# 5_Current_Voltage_Sensor.net
KiCad netlist of a schematic drawn in Altium Designer
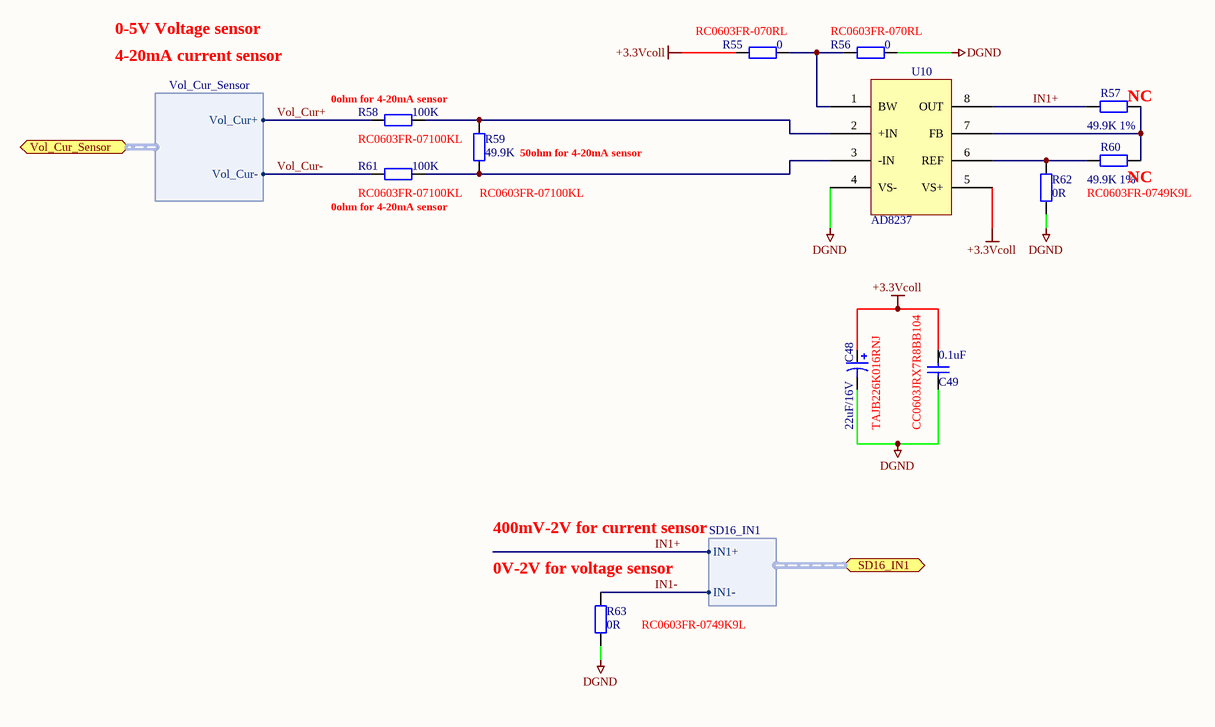
[diagram p0: 5_Current_Voltage_Sensor.SchDoc]

(export (version "E")
  (design (tool "Eeschema 10.0.6"))
  (components
    (comp (ref "C48")
      (value "22uF/16V")
      (footprint "CB3528")
      (description "Polarized Capacitor (Radial)")
      (fields (field (name "PART NO.") "TAJB226K016RNJ"))
      (libsource (lib "Miscellaneous Devices") (part "Cap Pol1"))
    )
    (comp (ref "C49")
      (value "0.1uF")
      (footprint "CC0603")
      (description "Capacitor")
      (fields (field (name "TYPE NO.") "CC0603JRX7R8BB104"))
      (libsource (lib "Miscellaneous Devices") (part "Cap"))
    )
    (comp (ref "R55")
      (value "0")
      (footprint "CC0603")
      (description "Resistor")
      (fields (field (name "TYPE NO.") "RC0603FR-070RL"))
      (libsource (lib "Miscellaneous Devices") (part "Res2"))
    )
    (comp (ref "R56")
      (value "0")
      (footprint "CC0603")
      (description "Resistor")
      (fields (field (name "TYPE NO.") "RC0603FR-070RL"))
      (libsource (lib "Miscellaneous Devices") (part "Res2"))
    )
    (comp (ref "R57")
      (value "49.9K 1%")
      (footprint "CC0603")
      (description "Resistor")
      (fields (field (name "PUBLISHER") "Altium Limited"))
      (libsource (lib "Miscellaneous Devices") (part "Res2"))
    )
    (comp (ref "R58")
      (value "100K")
      (footprint "CC0603")
      (description "Resistor")
      (fields (field (name "TYPE NO.") "RC0603FR-07100KL"))
      (libsource (lib "Miscellaneous Devices") (part "Res2"))
    )
    (comp (ref "R59")
      (value "49.9K")
      (footprint "CC0603")
      (description "Resistor")
      (fields (field (name "TYPE NO.") "RC0603FR-07100KL"))
      (libsource (lib "") (part "Res2_1"))
    )
    (comp (ref "R60")
      (value "49.9K 1%")
      (footprint "CC0603")
      (description "Resistor")
      (fields (field (name "PUBLISHER") "Altium Limited"))
      (libsource (lib "Miscellaneous Devices") (part "Res2"))
    )
    (comp (ref "R61")
      (value "100K")
      (footprint "CC0603")
      (description "Resistor")
      (fields (field (name "TYPE NO.") "RC0603FR-07100KL"))
      (libsource (lib "Miscellaneous Devices") (part "Res2"))
    )
    (comp (ref "R62")
      (value "0R")
      (footprint "CC0603")
      (description "Resistor")
      (fields (field (name "TYPE NO.") "RC0603FR-0749K9L"))
      (libsource (lib "") (part "Res2_1"))
    )
    (comp (ref "R63")
      (value "0R")
      (footprint "CC0603")
      (description "Resistor")
      (fields (field (name "TYPE NO.") "RC0603FR-0749K9L"))
      (libsource (lib "") (part "Res2_1"))
    )
    (comp (ref "U10") (value "AD8237") (footprint "MSOP8") (libsource (lib "woylib2015") (part "AD8237")))
  )
  (nets
    (net (code "3") (name "+3.3Vcoll") (class "Default")
      (node (ref "C48") (pin "1") (pinfunction "1_1") (pintype "passive"))
      (node (ref "C49") (pin "2") (pinfunction "2_2") (pintype "passive"))
      (node (ref "R55") (pin "2") (pinfunction "2_2") (pintype "passive"))
      (node (ref "U10") (pin "5") (pinfunction "VS+_5") (pintype "passive"))
    )
    (net (code "4") (name "/IN1+") (class "Default")
      (node (ref "R57") (pin "2") (pinfunction "2_2") (pintype "passive"))
      (node (ref "U10") (pin "8") (pinfunction "OUT_8") (pintype "passive"))
    )
    (net (code "5") (name "/IN1-") (class "Default")
      (node (ref "R63") (pin "1") (pinfunction "1_1") (pintype "passive"))
    )
    (net (code "6") (name "/Vol_Cur+") (class "Default")
      (node (ref "R58") (pin "2") (pinfunction "2_2") (pintype "passive"))
    )
    (net (code "7") (name "/Vol_Cur-") (class "Default")
      (node (ref "R61") (pin "2") (pinfunction "2_2") (pintype "passive"))
    )
    (net (code "10") (name "DGND") (class "Default")
      (node (ref "C48") (pin "2") (pinfunction "2_2") (pintype "passive"))
      (node (ref "C49") (pin "1") (pinfunction "1_1") (pintype "passive"))
      (node (ref "R56") (pin "1") (pinfunction "1_1") (pintype "passive"))
      (node (ref "R62") (pin "2") (pinfunction "2_2") (pintype "passive"))
      (node (ref "R63") (pin "2") (pinfunction "2_2") (pintype "passive"))
      (node (ref "U10") (pin "4") (pinfunction "VS-_4") (pintype "passive"))
    )
    (net (code "11") (name "Net-(U10-+IN)") (class "Default")
      (node (ref "R58") (pin "1") (pinfunction "1_1") (pintype "passive"))
      (node (ref "R59") (pin "1") (pinfunction "1_1") (pintype "passive"))
      (node (ref "U10") (pin "2") (pinfunction "+IN_2") (pintype "passive"))
    )
    (net (code "12") (name "Net-(U10--IN)") (class "Default")
      (node (ref "R59") (pin "2") (pinfunction "2_2") (pintype "passive"))
      (node (ref "R61") (pin "1") (pinfunction "1_1") (pintype "passive"))
      (node (ref "U10") (pin "3") (pinfunction "-IN_3") (pintype "passive"))
    )
    (net (code "13") (name "Net-(U10-BW)") (class "Default")
      (node (ref "R55") (pin "1") (pinfunction "1_1") (pintype "passive"))
      (node (ref "R56") (pin "2") (pinfunction "2_2") (pintype "passive"))
      (node (ref "U10") (pin "1") (pinfunction "BW_1") (pintype "passive"))
    )
    (net (code "14") (name "Net-(U10-FB)") (class "Default")
      (node (ref "R57") (pin "1") (pinfunction "1_1") (pintype "passive"))
      (node (ref "R60") (pin "1") (pinfunction "1_1") (pintype "passive"))
      (node (ref "U10") (pin "7") (pinfunction "FB_7") (pintype "passive"))
    )
    (net (code "15") (name "Net-(U10-REF)") (class "Default")
      (node (ref "R60") (pin "2") (pinfunction "2_2") (pintype "passive"))
      (node (ref "R62") (pin "1") (pinfunction "1_1") (pintype "passive"))
      (node (ref "U10") (pin "6") (pinfunction "REF_6") (pintype "passive"))
    )
  )
)
